# PSUv2.net
KiCad netlist of a schematic drawn in Altium Designer
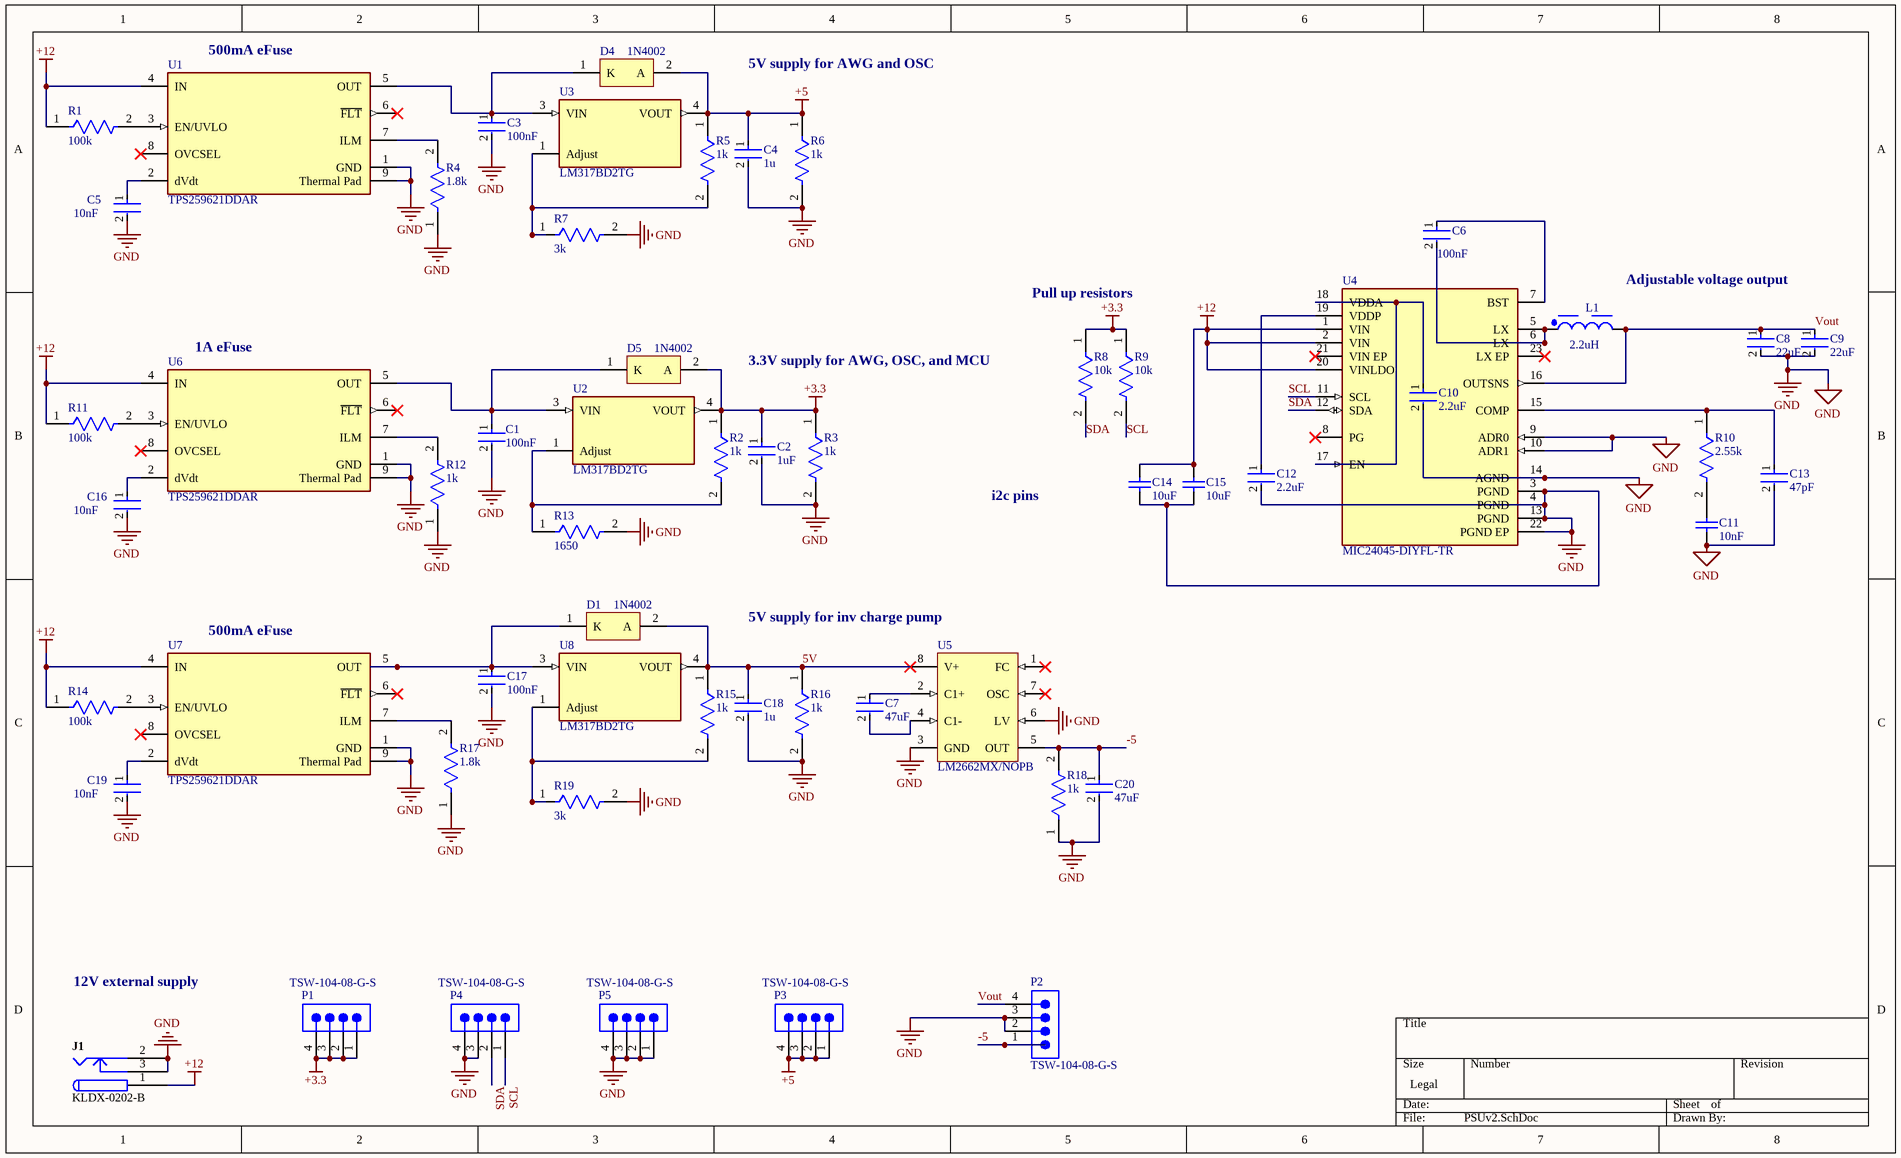
[diagram p0: PSUv2.SchDoc]

(export (version "E")
  (design (tool "Eeschema 10.0.6"))
  (components
    (comp (ref "C1")
      (value "100nF")
      (footprint "FP-CC0805-0_85-MFG")
      (description "CAP CER 0.1UF 25V X7R 0805")
      (fields (field (name "MANUFACTURER") "Yageo") (field (name "TOLERANCE") "0.2"))
      (libsource (lib "Altium Content Vault") (part "11868f565c42a9108669ba33697ecf6"))
    )
    (comp (ref "C2")
      (value "1uF")
      (footprint "FP-CC0805-0_85-MFG")
      (description "CAP CER 1UF 6.3V X5R 0805")
      (fields (field (name "MANUFACTURER") "Yageo") (field (name "TOLERANCE") "0.1"))
      (libsource (lib "Altium Content Vault") (part "11868f565c42a9108669ba33697ecf6"))
    )
    (comp (ref "C3")
      (value "100nF")
      (footprint "FP-CC0805-0_85-MFG")
      (description "CAP CER 0.1UF 25V X7R 0805")
      (fields (field (name "MANUFACTURER") "Yageo") (field (name "TOLERANCE") "0.2"))
      (libsource (lib "Altium Content Vault") (part "11868f565c42a9108669ba33697ecf6"))
    )
    (comp (ref "C4")
      (value "1u")
      (footprint "FP-CC0805-0_85-MFG")
      (description "CAP CER 1UF 6.3V X5R 0805")
      (fields (field (name "MANUFACTURER") "Yageo") (field (name "TOLERANCE") "0.1"))
      (libsource (lib "Altium Content Vault") (part "11868f565c42a9108669ba33697ecf6"))
    )
    (comp (ref "C5")
      (value "10nF")
      (footprint "FP-CC0805-0_85-MFG")
      (description "CAP CER 0.1UF 25V X7R 0805")
      (fields (field (name "MANUFACTURER") "Yageo") (field (name "TOLERANCE") "0.2"))
      (libsource (lib "Altium Content Vault") (part "11868f565c42a9108669ba33697ecf6"))
    )
    (comp (ref "C6")
      (value "100nF")
      (footprint "FP-CC0805-0_85-MFG")
      (description "CAP CER 0.1UF 25V X7R 0805")
      (fields (field (name "MANUFACTURER") "Yageo") (field (name "TOLERANCE") "0.2"))
      (libsource (lib "Altium Content Vault") (part "11868f565c42a9108669ba33697ecf6"))
    )
    (comp (ref "C7")
      (value "47uF")
      (footprint "FP-GRM21B-0_2-e0_2_0_7-IPC_A")
      (description "Chip Multilayer Ceramic Capacitors for General Purpose, 0805, 47uF, X5R, 15%, 20%, 10V")
      (fields (field (name "TOLERANCE") "20%") (field (name "VOLTAGE") "10V"))
      (libsource (lib "Altium Content Vault") (part "b4654b650e69147ec39a6b967a45e02"))
    )
    (comp (ref "C8")
      (value "22uF")
      (footprint "FP-C0805C226M8PACTU-MFG")
      (description "CAP CER 22UF 10V X5R 0805")
      (fields (field (name "TOLERANCE") "20%") (field (name "VOLTAGE") "10V"))
      (libsource (lib "Altium Content Vault") (part "02cd4be3c70576c341d710602a673aa"))
    )
    (comp (ref "C9")
      (value "22uF")
      (footprint "FP-C0805C226M8PACTU-MFG")
      (description "CAP CER 22UF 10V X5R 0805")
      (fields (field (name "TOLERANCE") "20%") (field (name "VOLTAGE") "10V"))
      (libsource (lib "Altium Content Vault") (part "02cd4be3c70576c341d710602a673aa"))
    )
    (comp (ref "C10")
      (value "2.2uF")
      (footprint "FP-CC0805-0_85-MFG")
      (description "CC0805 2.2 uF X5R 20.00% 10 V")
      (fields (field (name "MANUFACTURER PART NUMBER") "CC0805MKX5R6BB225"))
      (libsource (lib "Altium Content Vault") (part "11868f565c42a9108669ba33697ecf6"))
    )
    (comp (ref "C11")
      (value "10nF")
      (footprint "CAPC2013X94X50LL20T25")
      (fields
        (field (name "MANUFACTURER") "AVX Interconnect / Elco")
        (field (name "PART NUMBER") "08053C103JAT2A")
      )
      (libsource (lib "Altium Content Vault") (part "CAP"))
    )
    (comp (ref "C12")
      (value "2.2uF")
      (footprint "FP-CC0805-0_85-MFG")
      (description "CC0805 2.2 uF X5R 20.00% 10 V")
      (fields (field (name "MANUFACTURER PART NUMBER") "CC0805MKX5R6BB225"))
      (libsource (lib "Altium Content Vault") (part "11868f565c42a9108669ba33697ecf6"))
    )
    (comp (ref "C13")
      (value "47pF")
      (footprint "FP-C0805C-DN-MFG")
      (description "C0805 47 pF X7R 30ppm/°C 10.00% 50 V")
      (fields
        (field (name "MANUFACTURER") "KEMET")
        (field (name "OCTOPART") "https://octopart.com/c0805c470k5ractu-kemet-89187434")
      )
      (libsource (lib "Altium Content Vault") (part "b4654b650e69147ec39a6b967a45e02"))
    )
    (comp (ref "C14")
      (value "10uF")
      (footprint "CAPC2013X140X50ML20T25")
      (fields
        (field (name "PART NUMBER") "08056D106KAT4A")
        (field (name "MANUFACTURER") "AVX Interconnect / Elco")
      )
      (libsource (lib "Altium Content Vault") (part "CAP"))
    )
    (comp (ref "C15")
      (value "10uF")
      (footprint "CAPC2013X140X50ML20T25")
      (fields
        (field (name "PART NUMBER") "08056D106KAT4A")
        (field (name "MANUFACTURER") "AVX Interconnect / Elco")
      )
      (libsource (lib "Altium Content Vault") (part "CAP"))
    )
    (comp (ref "C16")
      (value "10nF")
      (footprint "FP-CC0805-0_85-MFG")
      (description "CAP CER 0.1UF 25V X7R 0805")
      (fields (field (name "MANUFACTURER") "Yageo") (field (name "TOLERANCE") "0.2"))
      (libsource (lib "Altium Content Vault") (part "11868f565c42a9108669ba33697ecf6"))
    )
    (comp (ref "C17")
      (value "100nF")
      (footprint "FP-CC0805-0_85-MFG")
      (description "CAP CER 0.1UF 25V X7R 0805")
      (fields (field (name "MANUFACTURER") "Yageo") (field (name "TOLERANCE") "0.2"))
      (libsource (lib "Altium Content Vault") (part "11868f565c42a9108669ba33697ecf6"))
    )
    (comp (ref "C18")
      (value "1u")
      (footprint "FP-CC0805-0_85-MFG")
      (description "CAP CER 1UF 6.3V X5R 0805")
      (fields (field (name "MANUFACTURER") "Yageo") (field (name "TOLERANCE") "0.1"))
      (libsource (lib "Altium Content Vault") (part "11868f565c42a9108669ba33697ecf6"))
    )
    (comp (ref "C19")
      (value "10nF")
      (footprint "FP-CC0805-0_85-MFG")
      (description "CAP CER 0.1UF 25V X7R 0805")
      (fields (field (name "MANUFACTURER") "Yageo") (field (name "TOLERANCE") "0.2"))
      (libsource (lib "Altium Content Vault") (part "11868f565c42a9108669ba33697ecf6"))
    )
    (comp (ref "C20")
      (value "47uF")
      (footprint "FP-GRM21B-0_2-e0_2_0_7-IPC_A")
      (description "Chip Multilayer Ceramic Capacitors for General Purpose, 0805, 47uF, X5R, 15%, 20%, 10V")
      (fields (field (name "TOLERANCE") "20%") (field (name "VOLTAGE") "10V"))
      (libsource (lib "Altium Content Vault") (part "b4654b650e69147ec39a6b967a45e02"))
    )
    (comp (ref "D1")
      (value "1N4002")
      (footprint "ONSC-AXIAL_LEAD-2-59-10_P")
      (description "Standard Recovery Rectifier, 2-Pin Axial_Lead, Pb-Free, Bulk Bag")
      (fields (field (name "MANUFACTURER") "On Semiconductor"))
      (libsource (lib "Altium Content Vault") (part "ONSC-D-K1A2-2_A"))
    )
    (comp (ref "D4")
      (value "1N4002")
      (footprint "ONSC-AXIAL_LEAD-2-59-10_P")
      (description "Standard Recovery Rectifier, 2-Pin Axial_Lead, Pb-Free, Bulk Bag")
      (fields (field (name "MANUFACTURER") "On Semiconductor"))
      (libsource (lib "Altium Content Vault") (part "ONSC-D-K1A2-2_A"))
    )
    (comp (ref "D5")
      (value "1N4002")
      (footprint "ONSC-AXIAL_LEAD-2-59-10_P")
      (description "Standard Recovery Rectifier, 2-Pin Axial_Lead, Pb-Free, Bulk Bag")
      (fields (field (name "MANUFACTURER") "On Semiconductor"))
      (libsource (lib "Altium Content Vault") (part "ONSC-D-K1A2-2_A"))
    )
    (comp (ref "J1")
      (value "KLDX-0202-B")
      (footprint "KYCN-KLDX-0202-B_V")
      (description "3 Conductor Power Jack, 2 break 2 aux contacts")
      (libsource (lib "Altium Content Vault") (part "KYCN-KLDX-0202-B-3"))
    )
    (comp (ref "L1")
      (value "2.2uH")
      (footprint "WE-LQS_6045")
      (description "Inductor Power Semi-Shielded Wirewound 2.2uH 30% 100KHz 4.6A 14mOhm DCR 2424 T/R")
      (fields (field (name "TOLERANCE") "30%"))
      (libsource (lib "Altium Content Vault") (part "Inductor - 2"))
    )
    (comp (ref "P1")
      (value "TSW-104-08-G-S")
      (footprint "SMTC-TSW-104-08-X-S")
      (description "0.025\" SQ Post Header, Through-hole, Vertical, -55 to 125 degC, 2.54 mm Pitch, 4-Pin, Male, RoHS")
      (fields (field (name "MANUFACTURER") "Samtec"))
      (libsource (lib "Altium Content Vault") (part "SMTC-TSW-104-08-X-S"))
    )
    (comp (ref "P2")
      (value "TSW-104-08-G-S")
      (footprint "SMTC-TSW-104-08-X-S")
      (description "0.025\" SQ Post Header, Through-hole, Vertical, -55 to 125 degC, 2.54 mm Pitch, 4-Pin, Male, RoHS")
      (fields (field (name "MANUFACTURER") "Samtec"))
      (libsource (lib "Altium Content Vault") (part "SMTC-TSW-104-08-X-S"))
    )
    (comp (ref "P3")
      (value "TSW-104-08-G-S")
      (footprint "SMTC-TSW-104-08-X-S")
      (description "0.025\" SQ Post Header, Through-hole, Vertical, -55 to 125 degC, 2.54 mm Pitch, 4-Pin, Male, RoHS")
      (fields (field (name "MANUFACTURER") "Samtec"))
      (libsource (lib "Altium Content Vault") (part "SMTC-TSW-104-08-X-S"))
    )
    (comp (ref "P4")
      (value "TSW-104-08-G-S")
      (footprint "SMTC-TSW-104-08-X-S")
      (description "0.025\" SQ Post Header, Through-hole, Vertical, -55 to 125 degC, 2.54 mm Pitch, 4-Pin, Male, RoHS")
      (fields (field (name "MANUFACTURER") "Samtec"))
      (libsource (lib "Altium Content Vault") (part "SMTC-TSW-104-08-X-S"))
    )
    (comp (ref "P5")
      (value "TSW-104-08-G-S")
      (footprint "SMTC-TSW-104-08-X-S")
      (description "0.025\" SQ Post Header, Through-hole, Vertical, -55 to 125 degC, 2.54 mm Pitch, 4-Pin, Male, RoHS")
      (fields (field (name "MANUFACTURER") "Samtec"))
      (libsource (lib "Altium Content Vault") (part "SMTC-TSW-104-08-X-S"))
    )
    (comp (ref "R1")
      (value "100k")
      (footprint "FP-RMCF0805-MFG")
      (description "1kΩ ±1% 0.125W 0805 Thick Film Chip Resistor AEC-Q200 compliant")
      (fields (field (name "TOLERANCE") "1%"))
      (libsource (lib "Altium Content Vault") (part "1029c3af85768c4190bb7ad29bc67b5"))
    )
    (comp (ref "R2")
      (value "1k")
      (footprint "FP-RMCF0805-MFG")
      (description "1kΩ ±1% 0.125W 0805 Thick Film Chip Resistor AEC-Q200 compliant")
      (fields (field (name "TOLERANCE") "1%"))
      (libsource (lib "Altium Content Vault") (part "1029c3af85768c4190bb7ad29bc67b5"))
    )
    (comp (ref "R3")
      (value "1k")
      (footprint "FP-RMCF0805-MFG")
      (description "1kΩ ±1% 0.125W 0805 Thick Film Chip Resistor AEC-Q200 compliant")
      (fields (field (name "TOLERANCE") "1%"))
      (libsource (lib "Altium Content Vault") (part "1029c3af85768c4190bb7ad29bc67b5"))
    )
    (comp (ref "R4")
      (value "1.8k")
      (footprint "FP-AC0805-MFG")
      (description "RES SMD 1.8K OHM 1% 1/8W 0805")
      (fields (field (name "MANUFACTURER") "Yageo") (field (name "TOLERANCE") "0.01"))
      (libsource (lib "Altium Content Vault") (part "1029c3af85768c4190bb7ad29bc67b5"))
    )
    (comp (ref "R5")
      (value "1k")
      (footprint "FP-RMCF0805-MFG")
      (description "1kΩ ±1% 0.125W 0805 Thick Film Chip Resistor AEC-Q200 compliant")
      (fields (field (name "TOLERANCE") "1%"))
      (libsource (lib "Altium Content Vault") (part "1029c3af85768c4190bb7ad29bc67b5"))
    )
    (comp (ref "R6")
      (value "1k")
      (footprint "FP-RMCF0805-MFG")
      (description "1kΩ ±1% 0.125W 0805 Thick Film Chip Resistor AEC-Q200 compliant")
      (fields (field (name "TOLERANCE") "1%"))
      (libsource (lib "Altium Content Vault") (part "1029c3af85768c4190bb7ad29bc67b5"))
    )
    (comp (ref "R7")
      (value "3k")
      (footprint "FP-RMCF0805-IPC_B")
      (description "3kΩ ±5% 0.125W 0805 Thick Film Chip Resistor AEC-Q200 compliant")
      (fields (field (name "TOLERANCE") "5%"))
      (libsource (lib "Altium Content Vault") (part "1029c3af85768c4190bb7ad29bc67b5"))
    )
    (comp (ref "R8")
      (value "10k")
      (footprint "FP-PATT0805-MFG")
      (description "RES SMD 10K OHM 0.1% 1/5W 0805")
      (fields (field (name "TOLERANCE") "0.1%") (field (name "MANUFACTURER PART NUMBER") "PATT0805E1002BGT1"))
      (libsource (lib "Altium Content Vault") (part "1029c3af85768c4190bb7ad29bc67b5"))
    )
    (comp (ref "R9")
      (value "10k")
      (footprint "FP-PATT0805-MFG")
      (description "RES SMD 10K OHM 0.1% 1/5W 0805")
      (fields (field (name "TOLERANCE") "0.1%") (field (name "MANUFACTURER PART NUMBER") "PATT0805E1002BGT1"))
      (libsource (lib "Altium Content Vault") (part "1029c3af85768c4190bb7ad29bc67b5"))
    )
    (comp (ref "R10")
      (value "2.55k")
      (footprint "FP-RMCF0805-IPC_B")
      (description "2.55kΩ ±1% 0.125W 0805 Thick Film Chip Resistor AEC-Q200 compliant")
      (fields (field (name "TOLERANCE") "1%"))
      (libsource (lib "Altium Content Vault") (part "1029c3af85768c4190bb7ad29bc67b5"))
    )
    (comp (ref "R11")
      (value "100k")
      (footprint "FP-RMCF0805-MFG")
      (description "1kΩ ±1% 0.125W 0805 Thick Film Chip Resistor AEC-Q200 compliant")
      (fields (field (name "TOLERANCE") "1%"))
      (libsource (lib "Altium Content Vault") (part "1029c3af85768c4190bb7ad29bc67b5"))
    )
    (comp (ref "R12")
      (value "1k")
      (footprint "FP-AC0805-MFG")
      (description "RES SMD 1.8K OHM 1% 1/8W 0805")
      (fields (field (name "MANUFACTURER") "Yageo") (field (name "TOLERANCE") "0.01"))
      (libsource (lib "Altium Content Vault") (part "1029c3af85768c4190bb7ad29bc67b5"))
    )
    (comp (ref "R13")
      (value "1650")
      (footprint "FP-RT0805-MFG")
      (description "RES SMD 1.65K OHM 1% 1/8W 0805")
      (fields
        (field (name "TOLERANCE") "0.0001")
        (field (name "OCTOPART") "https://octopart.com/rt0805fre071k65l-yageo-1226722")
      )
      (libsource (lib "Altium Content Vault") (part "1029c3af85768c4190bb7ad29bc67b5"))
    )
    (comp (ref "R14")
      (value "100k")
      (footprint "FP-RMCF0805-MFG")
      (description "1kΩ ±1% 0.125W 0805 Thick Film Chip Resistor AEC-Q200 compliant")
      (fields (field (name "TOLERANCE") "1%"))
      (libsource (lib "Altium Content Vault") (part "1029c3af85768c4190bb7ad29bc67b5"))
    )
    (comp (ref "R15")
      (value "1k")
      (footprint "FP-RMCF0805-MFG")
      (description "1kΩ ±1% 0.125W 0805 Thick Film Chip Resistor AEC-Q200 compliant")
      (fields (field (name "TOLERANCE") "1%"))
      (libsource (lib "Altium Content Vault") (part "1029c3af85768c4190bb7ad29bc67b5"))
    )
    (comp (ref "R16")
      (value "1k")
      (footprint "FP-RMCF0805-MFG")
      (description "1kΩ ±1% 0.125W 0805 Thick Film Chip Resistor AEC-Q200 compliant")
      (fields (field (name "TOLERANCE") "1%"))
      (libsource (lib "Altium Content Vault") (part "1029c3af85768c4190bb7ad29bc67b5"))
    )
    (comp (ref "R17")
      (value "1.8k")
      (footprint "FP-AC0805-MFG")
      (description "RES SMD 1.8K OHM 1% 1/8W 0805")
      (fields (field (name "MANUFACTURER") "Yageo") (field (name "TOLERANCE") "0.01"))
      (libsource (lib "Altium Content Vault") (part "1029c3af85768c4190bb7ad29bc67b5"))
    )
    (comp (ref "R18")
      (value "1k")
      (footprint "FP-RMCF0805-MFG")
      (description "1kΩ ±1% 0.125W 0805 Thick Film Chip Resistor AEC-Q200 compliant")
      (fields (field (name "TOLERANCE") "1%"))
      (libsource (lib "Altium Content Vault") (part "1029c3af85768c4190bb7ad29bc67b5"))
    )
    (comp (ref "R19")
      (value "3k")
      (footprint "FP-RMCF0805-IPC_B")
      (description "3kΩ ±5% 0.125W 0805 Thick Film Chip Resistor AEC-Q200 compliant")
      (fields (field (name "TOLERANCE") "5%"))
      (libsource (lib "Altium Content Vault") (part "1029c3af85768c4190bb7ad29bc67b5"))
    )
    (comp (ref "U1")
      (value "TPS259621DDAR")
      (footprint "FP-DDA0008J-IPC_A")
      (description "2.7-19V 130MA-2A SURGE CLAMPING")
      (libsource (lib "Altium Content Vault") (part "dcfcedcc3a9fb49b7817f2e200c0380"))
    )
    (comp (ref "U2")
      (value "LM317BD2TG")
      (footprint "FP-936-03-MFG")
      (description "IC REG LINEAR POS ADJ 1.5A D2PAK")
      (fields
        (field (name "MANUFACTURER") "ON Semiconductor")
        (field (name "OCTOPART") "https://octopart.com/lm317bd2tg-on+semiconductor-1010532")
      )
      (libsource (lib "Altium Content Vault") (part "3e266703f71d0bbfea699e6b61623e5"))
    )
    (comp (ref "U3")
      (value "LM317BD2TG")
      (footprint "FP-936-03-MFG")
      (description "IC REG LINEAR POS ADJ 1.5A D2PAK")
      (fields
        (field (name "MANUFACTURER") "ON Semiconductor")
        (field (name "OCTOPART") "https://octopart.com/lm317bd2tg-on+semiconductor-1010532")
      )
      (libsource (lib "Altium Content Vault") (part "3e266703f71d0bbfea699e6b61623e5"))
    )
    (comp (ref "U4")
      (value "MIC24045-DIYFL-TR")
      (footprint "FP-FQFN33-20LD-PL-1-MFG")
      (description "IC REG BUCK PROG 5A 20FQFN")
      (libsource (lib "Altium Content Vault") (part "2fa809bf5726f16dc5a173c1784f189"))
    )
    (comp (ref "U5")
      (value "LM2662MX/NOPB")
      (footprint "D0008A_M")
      (description "Switched Capacitor Voltage Converter, 8-pin Narrow SOIC, Pb-Free")
      (fields (field (name "MANUFACTURER") "Texas Instruments"))
      (libsource (lib "Altium Content Vault") (part "PM-CHP-LM2660M-8"))
    )
    (comp (ref "U6")
      (value "TPS259621DDAR")
      (footprint "FP-DDA0008J-IPC_A")
      (description "2.7-19V 130MA-2A SURGE CLAMPING")
      (libsource (lib "Altium Content Vault") (part "dcfcedcc3a9fb49b7817f2e200c0380"))
    )
    (comp (ref "U7")
      (value "TPS259621DDAR")
      (footprint "FP-DDA0008J-IPC_A")
      (description "2.7-19V 130MA-2A SURGE CLAMPING")
      (libsource (lib "Altium Content Vault") (part "dcfcedcc3a9fb49b7817f2e200c0380"))
    )
    (comp (ref "U8")
      (value "LM317BD2TG")
      (footprint "FP-936-03-MFG")
      (description "IC REG LINEAR POS ADJ 1.5A D2PAK")
      (fields
        (field (name "MANUFACTURER") "ON Semiconductor")
        (field (name "OCTOPART") "https://octopart.com/lm317bd2tg-on+semiconductor-1010532")
      )
      (libsource (lib "Altium Content Vault") (part "3e266703f71d0bbfea699e6b61623e5"))
    )
  )
  (nets
    (net (code "1") (name "+3.3") (class "Default")
      (node (ref "C2") (pin "1") (pinfunction "1_1") (pintype "passive"))
      (node (ref "D5") (pin "2") (pinfunction "A_2") (pintype "passive"))
      (node (ref "P1") (pin "1") (pinfunction "1_1") (pintype "passive"))
      (node (ref "P1") (pin "2") (pinfunction "2_2") (pintype "passive"))
      (node (ref "P1") (pin "3") (pinfunction "3_3") (pintype "passive"))
      (node (ref "P1") (pin "4") (pinfunction "4_4") (pintype "passive"))
      (node (ref "R2") (pin "1") (pinfunction "1_1") (pintype "passive"))
      (node (ref "R3") (pin "1") (pinfunction "1_1") (pintype "passive"))
      (node (ref "R8") (pin "1") (pinfunction "1_1") (pintype "passive"))
      (node (ref "R9") (pin "1") (pinfunction "1_1") (pintype "passive"))
      (node (ref "U2") (pin "4") (pinfunction "VOUT_4") (pintype "output"))
    )
    (net (code "2") (name "+5") (class "Default")
      (node (ref "C4") (pin "1") (pinfunction "1_1") (pintype "passive"))
      (node (ref "D4") (pin "2") (pinfunction "A_2") (pintype "passive"))
      (node (ref "P3") (pin "1") (pinfunction "1_1") (pintype "passive"))
      (node (ref "P3") (pin "2") (pinfunction "2_2") (pintype "passive"))
      (node (ref "P3") (pin "3") (pinfunction "3_3") (pintype "passive"))
      (node (ref "P3") (pin "4") (pinfunction "4_4") (pintype "passive"))
      (node (ref "R5") (pin "1") (pinfunction "1_1") (pintype "passive"))
      (node (ref "R6") (pin "1") (pinfunction "1_1") (pintype "passive"))
      (node (ref "U3") (pin "4") (pinfunction "VOUT_4") (pintype "output"))
    )
    (net (code "3") (name "+12") (class "Default")
      (node (ref "C14") (pin "2") (pinfunction "2_2") (pintype "passive"))
      (node (ref "C15") (pin "2") (pinfunction "2_2") (pintype "passive"))
      (node (ref "J1") (pin "1") (pintype "power_in"))
      (node (ref "R1") (pin "1") (pinfunction "1_1") (pintype "passive"))
      (node (ref "R11") (pin "1") (pinfunction "1_1") (pintype "passive"))
      (node (ref "R14") (pin "1") (pinfunction "1_1") (pintype "passive"))
      (node (ref "U1") (pin "4") (pinfunction "IN_4") (pintype "power_in"))
      (node (ref "U4") (pin "1") (pinfunction "VIN_1") (pintype "power_in"))
      (node (ref "U4") (pin "2") (pinfunction "VIN_2") (pintype "power_in"))
      (node (ref "U4") (pin "20") (pinfunction "VINLDO_20") (pintype "power_in"))
      (node (ref "U6") (pin "4") (pinfunction "IN_4") (pintype "power_in"))
      (node (ref "U7") (pin "4") (pinfunction "IN_4") (pintype "power_in"))
    )
    (net (code "4") (name "/-5") (class "Default")
      (node (ref "C20") (pin "1") (pinfunction "1_1") (pintype "passive"))
      (node (ref "P2") (pin "1") (pinfunction "1_1") (pintype "passive"))
      (node (ref "R18") (pin "2") (pinfunction "2_2") (pintype "passive"))
      (node (ref "U5") (pin "5") (pinfunction "OUT_5") (pintype "power_in"))
    )
    (net (code "5") (name "/5V") (class "Default")
      (node (ref "C18") (pin "1") (pinfunction "1_1") (pintype "passive"))
      (node (ref "D1") (pin "2") (pinfunction "A_2") (pintype "passive"))
      (node (ref "R15") (pin "1") (pinfunction "1_1") (pintype "passive"))
      (node (ref "R16") (pin "1") (pinfunction "1_1") (pintype "passive"))
      (node (ref "U5") (pin "8") (pinfunction "V+_8") (pintype "power_in"))
      (node (ref "U8") (pin "4") (pinfunction "VOUT_4") (pintype "output"))
    )
    (net (code "6") (name "/SCL") (class "Default")
      (node (ref "P4") (pin "1") (pinfunction "1_1") (pintype "passive"))
      (node (ref "R9") (pin "2") (pinfunction "2_2") (pintype "passive"))
      (node (ref "U4") (pin "11") (pinfunction "SCL_11") (pintype "input"))
    )
    (net (code "7") (name "/SDA") (class "Default")
      (node (ref "P4") (pin "2") (pinfunction "2_2") (pintype "passive"))
      (node (ref "R8") (pin "2") (pinfunction "2_2") (pintype "passive"))
      (node (ref "U4") (pin "12") (pinfunction "SDA_12") (pintype "bidirectional"))
    )
    (net (code "8") (name "/Vout") (class "Default")
      (node (ref "C8") (pin "1") (pinfunction "1_1") (pintype "passive"))
      (node (ref "C9") (pin "1") (pinfunction "1_1") (pintype "passive"))
      (node (ref "L1") (pin "2") (pinfunction "2_2") (pintype "passive"))
      (node (ref "P2") (pin "4") (pinfunction "4_4") (pintype "passive"))
      (node (ref "U4") (pin "16") (pinfunction "OUTSNS_16") (pintype "output"))
    )
    (net (code "9") (name "GND") (class "Default")
      (node (ref "C1") (pin "2") (pinfunction "2_2") (pintype "passive"))
      (node (ref "C10") (pin "2") (pinfunction "2_2") (pintype "passive"))
      (node (ref "C11") (pin "2") (pinfunction "2_2") (pintype "passive"))
      (node (ref "C12") (pin "2") (pinfunction "2_2") (pintype "passive"))
      (node (ref "C13") (pin "2") (pinfunction "2_2") (pintype "passive"))
      (node (ref "C14") (pin "1") (pinfunction "1_1") (pintype "passive"))
      (node (ref "C15") (pin "1") (pinfunction "1_1") (pintype "passive"))
      (node (ref "C16") (pin "2") (pinfunction "2_2") (pintype "passive"))
      (node (ref "C17") (pin "2") (pinfunction "2_2") (pintype "passive"))
      (node (ref "C18") (pin "2") (pinfunction "2_2") (pintype "passive"))
      (node (ref "C19") (pin "2") (pinfunction "2_2") (pintype "passive"))
      (node (ref "C2") (pin "2") (pinfunction "2_2") (pintype "passive"))
      (node (ref "C20") (pin "2") (pinfunction "2_2") (pintype "passive"))
      (node (ref "C3") (pin "2") (pinfunction "2_2") (pintype "passive"))
      (node (ref "C4") (pin "2") (pinfunction "2_2") (pintype "passive"))
      (node (ref "C5") (pin "2") (pinfunction "2_2") (pintype "passive"))
      (node (ref "C8") (pin "2") (pinfunction "2_2") (pintype "passive"))
      (node (ref "C9") (pin "2") (pinfunction "2_2") (pintype "passive"))
      (node (ref "J1") (pin "2") (pintype "power_in"))
      (node (ref "J1") (pin "3") (pintype "power_in"))
      (node (ref "P2") (pin "2") (pinfunction "2_2") (pintype "passive"))
      (node (ref "P2") (pin "3") (pinfunction "3_3") (pintype "passive"))
      (node (ref "P4") (pin "3") (pinfunction "3_3") (pintype "passive"))
      (node (ref "P4") (pin "4") (pinfunction "4_4") (pintype "passive"))
      (node (ref "P5") (pin "1") (pinfunction "1_1") (pintype "passive"))
      (node (ref "P5") (pin "2") (pinfunction "2_2") (pintype "passive"))
      (node (ref "P5") (pin "3") (pinfunction "3_3") (pintype "passive"))
      (node (ref "P5") (pin "4") (pinfunction "4_4") (pintype "passive"))
      (node (ref "R12") (pin "1") (pinfunction "1_1") (pintype "passive"))
      (node (ref "R13") (pin "2") (pinfunction "2_2") (pintype "passive"))
      (node (ref "R16") (pin "2") (pinfunction "2_2") (pintype "passive"))
      (node (ref "R17") (pin "1") (pinfunction "1_1") (pintype "passive"))
      (node (ref "R18") (pin "1") (pinfunction "1_1") (pintype "passive"))
      (node (ref "R19") (pin "2") (pinfunction "2_2") (pintype "passive"))
      (node (ref "R3") (pin "2") (pinfunction "2_2") (pintype "passive"))
      (node (ref "R4") (pin "1") (pinfunction "1_1") (pintype "passive"))
      (node (ref "R6") (pin "2") (pinfunction "2_2") (pintype "passive"))
      (node (ref "R7") (pin "2") (pinfunction "2_2") (pintype "passive"))
      (node (ref "U1") (pin "1") (pinfunction "GND_1") (pintype "power_in"))
      (node (ref "U1") (pin "9") (pinfunction "Thermal_Pad_9") (pintype "passive"))
      (node (ref "U4") (pin "10") (pinfunction "ADR1_10") (pintype "input"))
      (node (ref "U4") (pin "13") (pinfunction "PGND_13") (pintype "power_in"))
      (node (ref "U4") (pin "14") (pinfunction "AGND_14") (pintype "power_in"))
      (node (ref "U4") (pin "22") (pinfunction "PGND_EP_22") (pintype "power_in"))
      (node (ref "U4") (pin "3") (pinfunction "PGND_3") (pintype "power_in"))
      (node (ref "U4") (pin "4") (pinfunction "PGND_4") (pintype "power_in"))
      (node (ref "U4") (pin "9") (pinfunction "ADR0_9") (pintype "input"))
      (node (ref "U5") (pin "3") (pinfunction "GND_3") (pintype "power_in"))
      (node (ref "U5") (pin "6") (pinfunction "LV_6") (pintype "input"))
      (node (ref "U6") (pin "1") (pinfunction "GND_1") (pintype "power_in"))
      (node (ref "U6") (pin "9") (pinfunction "Thermal_Pad_9") (pintype "passive"))
      (node (ref "U7") (pin "1") (pinfunction "GND_1") (pintype "power_in"))
      (node (ref "U7") (pin "9") (pinfunction "Thermal_Pad_9") (pintype "passive"))
    )
    (net (code "10") (name "Net-(C6-Pad2)") (class "Default")
      (node (ref "C6") (pin "2") (pinfunction "2_2") (pintype "passive"))
      (node (ref "L1") (pin "1") (pinfunction "1_1") (pintype "passive"))
      (node (ref "U4") (pin "5") (pinfunction "LX_5") (pintype "passive"))
      (node (ref "U4") (pin "6") (pinfunction "LX_6") (pintype "passive"))
    )
    (net (code "11") (name "Net-(C11-Pad1)") (class "Default")
      (node (ref "C11") (pin "1") (pinfunction "1_1") (pintype "passive"))
      (node (ref "R10") (pin "2") (pinfunction "2_2") (pintype "passive"))
    )
    (net (code "12") (name "Net-(D1-K)") (class "Default")
      (node (ref "C17") (pin "1") (pinfunction "1_1") (pintype "passive"))
      (node (ref "D1") (pin "1") (pinfunction "K_1") (pintype "passive"))
      (node (ref "U7") (pin "5") (pinfunction "OUT_5") (pintype "passive"))
      (node (ref "U8") (pin "3") (pinfunction "VIN_3") (pintype "input"))
    )
    (net (code "13") (name "Net-(D4-K)") (class "Default")
      (node (ref "C3") (pin "1") (pinfunction "1_1") (pintype "passive"))
      (node (ref "D4") (pin "1") (pinfunction "K_1") (pintype "passive"))
      (node (ref "U1") (pin "5") (pinfunction "OUT_5") (pintype "passive"))
      (node (ref "U3") (pin "3") (pinfunction "VIN_3") (pintype "input"))
    )
    (net (code "14") (name "Net-(D5-K)") (class "Default")
      (node (ref "C1") (pin "1") (pinfunction "1_1") (pintype "passive"))
      (node (ref "D5") (pin "1") (pinfunction "K_1") (pintype "passive"))
      (node (ref "U2") (pin "3") (pinfunction "VIN_3") (pintype "input"))
      (node (ref "U6") (pin "5") (pinfunction "OUT_5") (pintype "passive"))
    )
    (net (code "15") (name "Net-(U1-EN{slash}UVLO)") (class "Default")
      (node (ref "R1") (pin "2") (pinfunction "2_2") (pintype "passive"))
      (node (ref "U1") (pin "3") (pinfunction "EN/UVLO_3") (pintype "input"))
    )
    (net (code "16") (name "Net-(U1-ILM)") (class "Default")
      (node (ref "R4") (pin "2") (pinfunction "2_2") (pintype "passive"))
      (node (ref "U1") (pin "7") (pinfunction "ILM_7") (pintype "passive"))
    )
    (net (code "17") (name "Net-(U1-dVdt)") (class "Default")
      (node (ref "C5") (pin "1") (pinfunction "1_1") (pintype "passive"))
      (node (ref "U1") (pin "2") (pinfunction "dVdt_2") (pintype "passive"))
    )
    (net (code "18") (name "Net-(U2-Adjust)") (class "Default")
      (node (ref "R13") (pin "1") (pinfunction "1_1") (pintype "passive"))
      (node (ref "R2") (pin "2") (pinfunction "2_2") (pintype "passive"))
      (node (ref "U2") (pin "1") (pinfunction "Adjust_1") (pintype "passive"))
    )
    (net (code "19") (name "Net-(U3-Adjust)") (class "Default")
      (node (ref "R5") (pin "2") (pinfunction "2_2") (pintype "passive"))
      (node (ref "R7") (pin "1") (pinfunction "1_1") (pintype "passive"))
      (node (ref "U3") (pin "1") (pinfunction "Adjust_1") (pintype "passive"))
    )
    (net (code "20") (name "Net-(U4-BST)") (class "Default")
      (node (ref "C6") (pin "1") (pinfunction "1_1") (pintype "passive"))
      (node (ref "U4") (pin "7") (pinfunction "BST_7") (pintype "passive"))
    )
    (net (code "21") (name "Net-(U4-COMP)") (class "Default")
      (node (ref "C13") (pin "1") (pinfunction "1_1") (pintype "passive"))
      (node (ref "R10") (pin "1") (pinfunction "1_1") (pintype "passive"))
      (node (ref "U4") (pin "15") (pinfunction "COMP_15") (pintype "passive"))
    )
    (net (code "22") (name "Net-(U4-EN)") (class "Default")
      (node (ref "C10") (pin "1") (pinfunction "1_1") (pintype "passive"))
      (node (ref "U4") (pin "17") (pinfunction "EN_17") (pintype "input"))
      (node (ref "U4") (pin "18") (pinfunction "VDDA_18") (pintype "power_in"))
    )
    (net (code "23") (name "Net-(U4-VDDP)") (class "Default")
      (node (ref "C12") (pin "1") (pinfunction "1_1") (pintype "passive"))
      (node (ref "U4") (pin "19") (pinfunction "VDDP_19") (pintype "power_in"))
    )
    (net (code "24") (name "Net-(U5-C1+)") (class "Default")
      (node (ref "C7") (pin "1") (pinfunction "1_1") (pintype "passive"))
      (node (ref "U5") (pin "2") (pinfunction "C1+_2") (pintype "input"))
    )
    (net (code "25") (name "Net-(U5-C1-)") (class "Default")
      (node (ref "C7") (pin "2") (pinfunction "2_2") (pintype "passive"))
      (node (ref "U5") (pin "4") (pinfunction "C1-_4") (pintype "input"))
    )
    (net (code "26") (name "Net-(U6-EN{slash}UVLO)") (class "Default")
      (node (ref "R11") (pin "2") (pinfunction "2_2") (pintype "passive"))
      (node (ref "U6") (pin "3") (pinfunction "EN/UVLO_3") (pintype "input"))
    )
    (net (code "27") (name "Net-(U6-ILM)") (class "Default")
      (node (ref "R12") (pin "2") (pinfunction "2_2") (pintype "passive"))
      (node (ref "U6") (pin "7") (pinfunction "ILM_7") (pintype "passive"))
    )
    (net (code "28") (name "Net-(U6-dVdt)") (class "Default")
      (node (ref "C16") (pin "1") (pinfunction "1_1") (pintype "passive"))
      (node (ref "U6") (pin "2") (pinfunction "dVdt_2") (pintype "passive"))
    )
    (net (code "29") (name "Net-(U7-EN{slash}UVLO)") (class "Default")
      (node (ref "R14") (pin "2") (pinfunction "2_2") (pintype "passive"))
      (node (ref "U7") (pin "3") (pinfunction "EN/UVLO_3") (pintype "input"))
    )
    (net (code "30") (name "Net-(U7-ILM)") (class "Default")
      (node (ref "R17") (pin "2") (pinfunction "2_2") (pintype "passive"))
      (node (ref "U7") (pin "7") (pinfunction "ILM_7") (pintype "passive"))
    )
    (net (code "31") (name "Net-(U7-dVdt)") (class "Default")
      (node (ref "C19") (pin "1") (pinfunction "1_1") (pintype "passive"))
      (node (ref "U7") (pin "2") (pinfunction "dVdt_2") (pintype "passive"))
    )
    (net (code "32") (name "Net-(U8-Adjust)") (class "Default")
      (node (ref "R15") (pin "2") (pinfunction "2_2") (pintype "passive"))
      (node (ref "R19") (pin "1") (pinfunction "1_1") (pintype "passive"))
      (node (ref "U8") (pin "1") (pinfunction "Adjust_1") (pintype "passive"))
    )
    (net (code "33") (name "unconnected-(U1-OVCSEL-Pad8)") (class "Default")
      (node (ref "U1") (pin "8") (pinfunction "OVCSEL_8") (pintype "passive+no_connect"))
    )
    (net (code "34") (name "unconnected-(U1-~{FLT}-Pad6)") (class "Default")
      (node (ref "U1") (pin "6") (pinfunction "~{FLT}_6") (pintype "output+no_connect"))
    )
    (net (code "35") (name "unconnected-(U4-LX_EP-Pad23)") (class "Default")
      (node (ref "U4") (pin "23") (pinfunction "LX_EP_23") (pintype "passive+no_connect"))
    )
    (net (code "36") (name "unconnected-(U4-PG-Pad8)") (class "Default")
      (node (ref "U4") (pin "8") (pinfunction "PG_8") (pintype "open_collector+no_connect"))
    )
    (net (code "37") (name "unconnected-(U4-VIN_EP-Pad21)") (class "Default")
      (node (ref "U4") (pin "21") (pinfunction "VIN_EP_21") (pintype "power_in+no_connect"))
    )
    (net (code "38") (name "unconnected-(U5-FC-Pad1)") (class "Default")
      (node (ref "U5") (pin "1") (pinfunction "FC_1") (pintype "input+no_connect"))
    )
    (net (code "39") (name "unconnected-(U5-OSC-Pad7)") (class "Default")
      (node (ref "U5") (pin "7") (pinfunction "OSC_7") (pintype "input+no_connect"))
    )
    (net (code "40") (name "unconnected-(U6-OVCSEL-Pad8)") (class "Default")
      (node (ref "U6") (pin "8") (pinfunction "OVCSEL_8") (pintype "passive+no_connect"))
    )
    (net (code "41") (name "unconnected-(U6-~{FLT}-Pad6)") (class "Default")
      (node (ref "U6") (pin "6") (pinfunction "~{FLT}_6") (pintype "output+no_connect"))
    )
    (net (code "42") (name "unconnected-(U7-OVCSEL-Pad8)") (class "Default")
      (node (ref "U7") (pin "8") (pinfunction "OVCSEL_8") (pintype "passive+no_connect"))
    )
    (net (code "43") (name "unconnected-(U7-~{FLT}-Pad6)") (class "Default")
      (node (ref "U7") (pin "6") (pinfunction "~{FLT}_6") (pintype "output+no_connect"))
    )
  )
)
